# HT_Device.net
KiCad netlist of a schematic drawn in Altium Designer
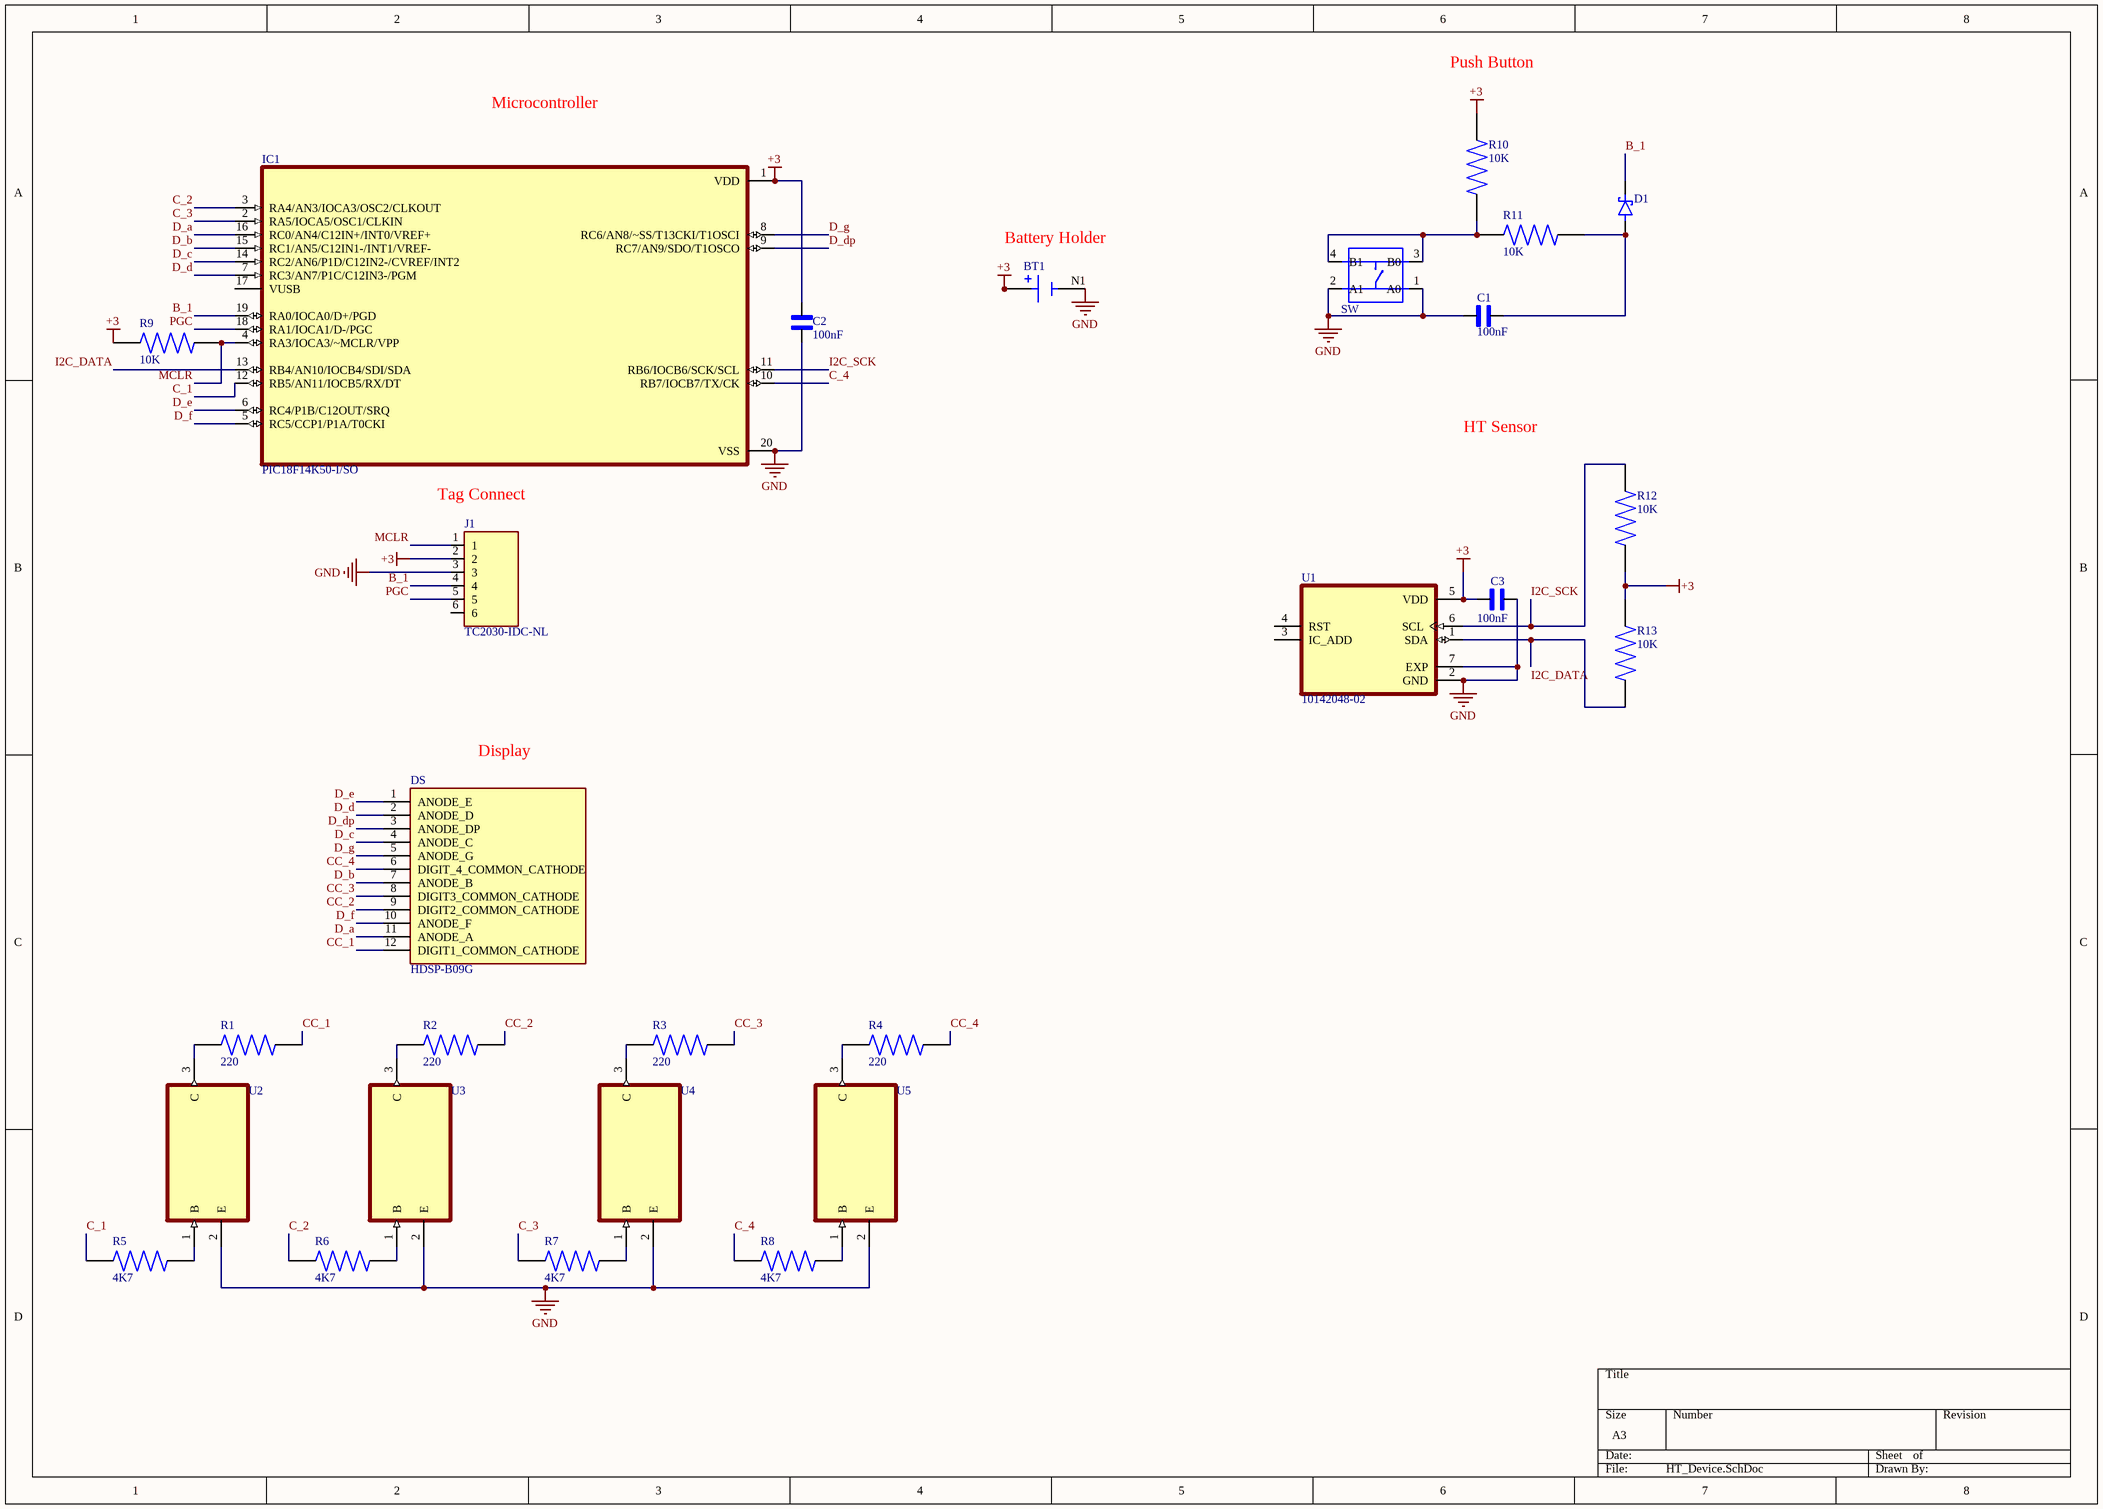
[diagram p0: HT_Device.SchDoc]

(export (version "E")
  (design (tool "Eeschema 10.0.6"))
  (components
    (comp (ref "BT1")
      (value "BAT-HLD-001")
      (footprint "BAT_BAT-HLD-001")
      (description "Battery Retainer Coin, 20.0mm 1 Cell SMD (SMT) Tab")
      (libsource (lib "BatteryHolder_CR2032") (part "BAT-HLD-001"))
    )
    (comp (ref "C1")
      (value "100nF")
      (footprint "WCAP-CSGP_885012207128")
      (fields (field (name "MP") "885012207128"))
      (libsource (lib "Capacitor_100nF_0805") (part "885012207128"))
    )
    (comp (ref "C2")
      (value "100nF")
      (footprint "WCAP-CSGP_885012207128")
      (fields (field (name "MP") "885012207128"))
      (libsource (lib "") (part "885012207128_1"))
    )
    (comp (ref "C3")
      (value "100nF")
      (footprint "WCAP-CSGP_885012207128")
      (fields (field (name "MP") "885012207128"))
      (libsource (lib "Capacitor_100nF_0805") (part "885012207128"))
    )
    (comp (ref "D1")
      (value "1N5817-T")
      (footprint "DIOAD1039W78L463D236")
      (description "Diode Schottky 20 V 1A Through Hole DO-41")
      (fields (field (name "MF") "Diodes Inc."))
      (libsource (lib "Diode_Rectifier_Schottky02") (part "1N5817-T"))
    )
    (comp (ref "DS")
      (value "HDSP-B09G")
      (footprint "AVAGO_HDSP-B09G")
      (fields (field (name "MF") "Broadcom Limited"))
      (libsource (lib "7Segment_4DigitalDisplay") (part "HDSP-B09G"))
    )
    (comp (ref "IC1")
      (value "PIC18F14K50-I/SO")
      (footprint "SOIC127P1032X265-20N")
      (description "PIC PICÂ® XLPâ„¢ 18K Microcontroller IC 8-Bit 48MHz 16KB _8K x 16_ FLASH 20-SOIC")
      (fields (field (name "MF") "Microchip"))
      (libsource (lib "SnapEDAsch") (part "PIC18F14K50-I/SO"))
    )
    (comp (ref "J1")
      (value "TC2030-IDC-NL")
      (footprint "TAG_TC2030-IDC-NL")
      (description "CABLE ADAPTER 6 POS")
      (libsource (lib "TagConnectPin_TC2030-IDC-NL") (part "TC2030-IDC-NL"))
    )
    (comp (ref "R1")
      (value "220")
      (footprint "RES_ERJP06J221V")
      (fields (field (name "MP") "ERJP06J221V"))
      (libsource (lib "Resistor_220_0805") (part "ERJP06J221V"))
    )
    (comp (ref "R2")
      (value "220")
      (footprint "RES_ERJP06J221V")
      (fields (field (name "MP") "ERJP06J221V"))
      (libsource (lib "Resistor_220_0805") (part "ERJP06J221V"))
    )
    (comp (ref "R3")
      (value "220")
      (footprint "RES_ERJP06J221V")
      (fields (field (name "MP") "ERJP06J221V"))
      (libsource (lib "Resistor_220_0805") (part "ERJP06J221V"))
    )
    (comp (ref "R4")
      (value "220")
      (footprint "RES_ERJP06J221V")
      (fields (field (name "MP") "ERJP06J221V"))
      (libsource (lib "Resistor_220_0805") (part "ERJP06J221V"))
    )
    (comp (ref "R5")
      (value "4K7")
      (footprint "RESC2012X55N")
      (fields (field (name "MP") "TNPW08054K70BXTA"))
      (libsource (lib "Resistor_4K7_0805") (part "TNPW08054K70BXTA"))
    )
    (comp (ref "R6")
      (value "4K7")
      (footprint "RESC2012X55N")
      (fields (field (name "MP") "TNPW08054K70BXTA"))
      (libsource (lib "Resistor_4K7_0805") (part "TNPW08054K70BXTA"))
    )
    (comp (ref "R7")
      (value "4K7")
      (footprint "RESC2012X55N")
      (fields (field (name "MP") "TNPW08054K70BXTA"))
      (libsource (lib "Resistor_4K7_0805") (part "TNPW08054K70BXTA"))
    )
    (comp (ref "R8")
      (value "4K7")
      (footprint "RESC2012X55N")
      (fields (field (name "MP") "TNPW08054K70BXTA"))
      (libsource (lib "Resistor_4K7_0805") (part "TNPW08054K70BXTA"))
    )
    (comp (ref "R9")
      (value "10K")
      (footprint "RESC2012X65N")
      (description "CRG0805 1% 10K")
      (fields (field (name "MF") "TE Connectivity") (field (name "TOLERANCE") "1%"))
      (libsource (lib "Resistor_10K_0805") (part "CRG0805F10K"))
    )
    (comp (ref "R10")
      (value "10K")
      (footprint "RESC2012X65N")
      (description "CRG0805 1% 10K")
      (fields (field (name "MF") "TE Connectivity") (field (name "TOLERANCE") "1%"))
      (libsource (lib "Resistor_10K_0805") (part "CRG0805F10K"))
    )
    (comp (ref "R11")
      (value "10K")
      (footprint "RESC2012X65N")
      (description "CRG0805 1% 10K")
      (fields (field (name "MF") "TE Connectivity") (field (name "TOLERANCE") "1%"))
      (libsource (lib "Resistor_10K_0805") (part "CRG0805F10K"))
    )
    (comp (ref "R12")
      (value "10K")
      (footprint "RESC2012X65N")
      (description "CRG0805 1% 10K")
      (fields (field (name "MF") "TE Connectivity") (field (name "TOLERANCE") "1%"))
      (libsource (lib "Resistor_10K_0805") (part "CRG0805F10K"))
    )
    (comp (ref "R13")
      (value "10K")
      (footprint "RESC2012X65N")
      (description "CRG0805 1% 10K")
      (fields (field (name "MF") "TE Connectivity") (field (name "TOLERANCE") "1%"))
      (libsource (lib "Resistor_10K_0805") (part "CRG0805F10K"))
    )
    (comp (ref "SW")
      (value "SMD-BUTTON(4P-5.2X5.2X1.5MM-SKQGADE010)")
      (footprint "SW4-SMD-5.2X5.2X1.5MM")
      (description "Switch Tactile N.O. SPST Round Button Gull Wing 0.05A 12VDC 2.55N SMD T/R")
      (fields (field (name "MF") "ALPS") (field (name "MP") "SKQGADE010"))
      (libsource (lib "PushButton04_4Pin") (part "SMD-BUTTON(4P-5.2X5.2X1.5MM-SKQGADE010)"))
    )
    (comp (ref "U1")
      (value "10142048-02")
      (footprint "SON80P250X250X100-7N_10142048-02")
      (description "Digital Relative Humidity sensor with Temperature output")
      (libsource (lib "10142048-02") (part "10142048-02"))
    )
    (comp (ref "U2")
      (value "MMBT2222A-7-F")
      (footprint "SOT103P240X110-3N")
      (description "Bipolar _BJT_ Transistor NPN 40V 600mA 300MHz 310mW Surface Mount SOT-23-3")
      (fields (field (name "MF") "Diodes Inc.") (field (name "DIGI-KEY_PART_NUMBER") "MMBT2222A-FDICT-ND"))
      (libsource (lib "BJT_NPN_600mA") (part "MMBT2222A-7-F"))
    )
    (comp (ref "U3")
      (value "MMBT2222A-7-F")
      (footprint "SOT103P240X110-3N")
      (description "Bipolar _BJT_ Transistor NPN 40V 600mA 300MHz 310mW Surface Mount SOT-23-3")
      (fields (field (name "MF") "Diodes Inc.") (field (name "DIGI-KEY_PART_NUMBER") "MMBT2222A-FDICT-ND"))
      (libsource (lib "BJT_NPN_600mA") (part "MMBT2222A-7-F"))
    )
    (comp (ref "U4")
      (value "MMBT2222A-7-F")
      (footprint "SOT103P240X110-3N")
      (description "Bipolar _BJT_ Transistor NPN 40V 600mA 300MHz 310mW Surface Mount SOT-23-3")
      (fields (field (name "MF") "Diodes Inc.") (field (name "DIGI-KEY_PART_NUMBER") "MMBT2222A-FDICT-ND"))
      (libsource (lib "BJT_NPN_600mA") (part "MMBT2222A-7-F"))
    )
    (comp (ref "U5")
      (value "MMBT2222A-7-F")
      (footprint "SOT103P240X110-3N")
      (description "Bipolar _BJT_ Transistor NPN 40V 600mA 300MHz 310mW Surface Mount SOT-23-3")
      (fields (field (name "MF") "Diodes Inc.") (field (name "DIGI-KEY_PART_NUMBER") "MMBT2222A-FDICT-ND"))
      (libsource (lib "BJT_NPN_600mA") (part "MMBT2222A-7-F"))
    )
  )
  (nets
    (net (code "1") (name "+3") (class "Default")
      (node (ref "BT1") (pin "P1") (pinfunction "POS_P1") (pintype "passive"))
      (node (ref "BT1") (pin "P2") (pinfunction "POS_P2") (pintype "passive"))
      (node (ref "C2") (pin "2") (pinfunction "2_2") (pintype "passive"))
      (node (ref "C3") (pin "2") (pinfunction "2_2") (pintype "passive"))
      (node (ref "IC1") (pin "1") (pinfunction "VDD_1") (pintype "power_in"))
      (node (ref "J1") (pin "2") (pinfunction "2_2") (pintype "passive"))
      (node (ref "R10") (pin "2") (pinfunction "2_2") (pintype "passive"))
      (node (ref "R12") (pin "1") (pinfunction "1_1") (pintype "passive"))
      (node (ref "R13") (pin "2") (pinfunction "2_2") (pintype "passive"))
      (node (ref "R9") (pin "1") (pinfunction "1_1") (pintype "passive"))
      (node (ref "U1") (pin "5") (pinfunction "VDD_5") (pintype "power_in"))
    )
    (net (code "2") (name "/B_1") (class "Default")
      (node (ref "D1") (pin "1") (pinfunction "K_1") (pintype "passive"))
      (node (ref "IC1") (pin "19") (pinfunction "RA0/IOCA0/D+/PGD_19") (pintype "bidirectional"))
      (node (ref "J1") (pin "4") (pinfunction "4_4") (pintype "passive"))
    )
    (net (code "3") (name "/CC_1") (class "Default")
      (node (ref "DS") (pin "12") (pinfunction "DIGIT1_COMMON_CATHODE_12") (pintype "passive"))
      (node (ref "R1") (pin "2") (pinfunction "2_2") (pintype "passive"))
    )
    (net (code "4") (name "/CC_2") (class "Default")
      (node (ref "DS") (pin "9") (pinfunction "DIGIT2_COMMON_CATHODE_9") (pintype "passive"))
      (node (ref "R2") (pin "2") (pinfunction "2_2") (pintype "passive"))
    )
    (net (code "5") (name "/CC_3") (class "Default")
      (node (ref "DS") (pin "8") (pinfunction "DIGIT3_COMMON_CATHODE_8") (pintype "passive"))
      (node (ref "R3") (pin "2") (pinfunction "2_2") (pintype "passive"))
    )
    (net (code "6") (name "/CC_4") (class "Default")
      (node (ref "DS") (pin "6") (pinfunction "DIGIT_4_COMMON_CATHODE_6") (pintype "passive"))
      (node (ref "R4") (pin "2") (pinfunction "2_2") (pintype "passive"))
    )
    (net (code "7") (name "/C_1") (class "Default")
      (node (ref "IC1") (pin "12") (pinfunction "RB5/AN11/IOCB5/RX/DT_12") (pintype "bidirectional"))
      (node (ref "R5") (pin "1") (pinfunction "1_1") (pintype "passive"))
    )
    (net (code "8") (name "/C_2") (class "Default")
      (node (ref "IC1") (pin "3") (pinfunction "RA4/AN3/IOCA3/OSC2/CLKOUT_3") (pintype "input"))
      (node (ref "R6") (pin "1") (pinfunction "1_1") (pintype "passive"))
    )
    (net (code "9") (name "/C_3") (class "Default")
      (node (ref "IC1") (pin "2") (pinfunction "RA5/IOCA5/OSC1/CLKIN_2") (pintype "input"))
      (node (ref "R7") (pin "1") (pinfunction "1_1") (pintype "passive"))
    )
    (net (code "10") (name "/C_4") (class "Default")
      (node (ref "IC1") (pin "10") (pinfunction "RB7/IOCB7/TX/CK_10") (pintype "bidirectional"))
      (node (ref "R8") (pin "1") (pinfunction "1_1") (pintype "passive"))
    )
    (net (code "11") (name "/D_a") (class "Default")
      (node (ref "DS") (pin "11") (pinfunction "ANODE_A_11") (pintype "passive"))
      (node (ref "IC1") (pin "16") (pinfunction "RC0/AN4/C12IN+/INT0/VREF+_16") (pintype "input"))
    )
    (net (code "12") (name "/D_b") (class "Default")
      (node (ref "DS") (pin "7") (pinfunction "ANODE_B_7") (pintype "passive"))
      (node (ref "IC1") (pin "15") (pinfunction "RC1/AN5/C12IN1-/INT1/VREF-_15") (pintype "input"))
    )
    (net (code "13") (name "/D_c") (class "Default")
      (node (ref "DS") (pin "4") (pinfunction "ANODE_C_4") (pintype "passive"))
      (node (ref "IC1") (pin "14") (pinfunction "RC2/AN6/P1D/C12IN2-/CVREF/INT2_14") (pintype "input"))
    )
    (net (code "14") (name "/D_d") (class "Default")
      (node (ref "DS") (pin "2") (pinfunction "ANODE_D_2") (pintype "passive"))
      (node (ref "IC1") (pin "7") (pinfunction "RC3/AN7/P1C/C12IN3-/PGM_7") (pintype "input"))
    )
    (net (code "15") (name "/D_dp") (class "Default")
      (node (ref "DS") (pin "3") (pinfunction "ANODE_DP_3") (pintype "passive"))
      (node (ref "IC1") (pin "9") (pinfunction "RC7/AN9/SDO/T1OSCO_9") (pintype "bidirectional"))
    )
    (net (code "16") (name "/D_e") (class "Default")
      (node (ref "DS") (pin "1") (pinfunction "ANODE_E_1") (pintype "passive"))
      (node (ref "IC1") (pin "6") (pinfunction "RC4/P1B/C12OUT/SRQ_6") (pintype "bidirectional"))
    )
    (net (code "17") (name "/D_f") (class "Default")
      (node (ref "DS") (pin "10") (pinfunction "ANODE_F_10") (pintype "passive"))
      (node (ref "IC1") (pin "5") (pinfunction "RC5/CCP1/P1A/T0CKI_5") (pintype "bidirectional"))
    )
    (net (code "18") (name "/D_g") (class "Default")
      (node (ref "DS") (pin "5") (pinfunction "ANODE_G_5") (pintype "passive"))
      (node (ref "IC1") (pin "8") (pinfunction "RC6/AN8/~SS/T13CKI/T1OSCI_8") (pintype "bidirectional"))
    )
    (net (code "19") (name "/I2C_DATA") (class "Default")
      (node (ref "IC1") (pin "13") (pinfunction "RB4/AN10/IOCB4/SDI/SDA_13") (pintype "bidirectional"))
      (node (ref "R13") (pin "1") (pinfunction "1_1") (pintype "passive"))
      (node (ref "U1") (pin "1") (pinfunction "SDA_1") (pintype "bidirectional"))
    )
    (net (code "20") (name "/I2C_SCK") (class "Default")
      (node (ref "IC1") (pin "11") (pinfunction "RB6/IOCB6/SCK/SCL_11") (pintype "bidirectional"))
      (node (ref "R12") (pin "2") (pinfunction "2_2") (pintype "passive"))
      (node (ref "U1") (pin "6") (pinfunction "SCL_6") (pintype "input"))
    )
    (net (code "21") (name "/MCLR") (class "Default")
      (node (ref "IC1") (pin "4") (pinfunction "RA3/IOCA3/~MCLR/VPP_4") (pintype "bidirectional"))
      (node (ref "J1") (pin "1") (pinfunction "1_1") (pintype "passive"))
      (node (ref "R9") (pin "2") (pinfunction "2_2") (pintype "passive"))
    )
    (net (code "22") (name "/PGC") (class "Default")
      (node (ref "IC1") (pin "18") (pinfunction "RA1/IOCA1/D-/PGC_18") (pintype "bidirectional"))
      (node (ref "J1") (pin "5") (pinfunction "5_5") (pintype "passive"))
    )
    (net (code "23") (name "GND") (class "Default")
      (node (ref "BT1") (pin "N1") (pinfunction "NEG_N1") (pintype "passive"))
      (node (ref "C1") (pin "2") (pinfunction "2_2") (pintype "passive"))
      (node (ref "C2") (pin "1") (pinfunction "1_1") (pintype "passive"))
      (node (ref "C3") (pin "1") (pinfunction "1_1") (pintype "passive"))
      (node (ref "IC1") (pin "20") (pinfunction "VSS_20") (pintype "power_in"))
      (node (ref "J1") (pin "3") (pinfunction "3_3") (pintype "passive"))
      (node (ref "SW") (pin "1") (pinfunction "A0_1") (pintype "bidirectional"))
      (node (ref "SW") (pin "2") (pinfunction "A1_2") (pintype "bidirectional"))
      (node (ref "U1") (pin "2") (pinfunction "GND_2") (pintype "power_in"))
      (node (ref "U1") (pin "7") (pinfunction "EXP_7") (pintype "passive"))
      (node (ref "U2") (pin "2") (pinfunction "E_2") (pintype "passive"))
      (node (ref "U3") (pin "2") (pinfunction "E_2") (pintype "passive"))
      (node (ref "U4") (pin "2") (pinfunction "E_2") (pintype "passive"))
      (node (ref "U5") (pin "2") (pinfunction "E_2") (pintype "passive"))
    )
    (net (code "24") (name "Net-(D1-A)") (class "Default")
      (node (ref "C1") (pin "1") (pinfunction "1_1") (pintype "passive"))
      (node (ref "D1") (pin "2") (pinfunction "A_2") (pintype "passive"))
      (node (ref "R11") (pin "2") (pinfunction "2_2") (pintype "passive"))
    )
    (net (code "25") (name "Net-(SW-B0)") (class "Default")
      (node (ref "R10") (pin "1") (pinfunction "1_1") (pintype "passive"))
      (node (ref "R11") (pin "1") (pinfunction "1_1") (pintype "passive"))
      (node (ref "SW") (pin "3") (pinfunction "B0_3") (pintype "bidirectional"))
      (node (ref "SW") (pin "4") (pinfunction "B1_4") (pintype "bidirectional"))
    )
    (net (code "26") (name "Net-(U2-B)") (class "Default")
      (node (ref "R5") (pin "2") (pinfunction "2_2") (pintype "passive"))
      (node (ref "U2") (pin "1") (pinfunction "B_1") (pintype "input"))
    )
    (net (code "27") (name "Net-(U2-C)") (class "Default")
      (node (ref "R1") (pin "1") (pinfunction "1_1") (pintype "passive"))
      (node (ref "U2") (pin "3") (pinfunction "C_3") (pintype "output"))
    )
    (net (code "28") (name "Net-(U3-B)") (class "Default")
      (node (ref "R6") (pin "2") (pinfunction "2_2") (pintype "passive"))
      (node (ref "U3") (pin "1") (pinfunction "B_1") (pintype "input"))
    )
    (net (code "29") (name "Net-(U3-C)") (class "Default")
      (node (ref "R2") (pin "1") (pinfunction "1_1") (pintype "passive"))
      (node (ref "U3") (pin "3") (pinfunction "C_3") (pintype "output"))
    )
    (net (code "30") (name "Net-(U4-B)") (class "Default")
      (node (ref "R7") (pin "2") (pinfunction "2_2") (pintype "passive"))
      (node (ref "U4") (pin "1") (pinfunction "B_1") (pintype "input"))
    )
    (net (code "31") (name "Net-(U4-C)") (class "Default")
      (node (ref "R3") (pin "1") (pinfunction "1_1") (pintype "passive"))
      (node (ref "U4") (pin "3") (pinfunction "C_3") (pintype "output"))
    )
    (net (code "32") (name "Net-(U5-B)") (class "Default")
      (node (ref "R8") (pin "2") (pinfunction "2_2") (pintype "passive"))
      (node (ref "U5") (pin "1") (pinfunction "B_1") (pintype "input"))
    )
    (net (code "33") (name "Net-(U5-C)") (class "Default")
      (node (ref "R4") (pin "1") (pinfunction "1_1") (pintype "passive"))
      (node (ref "U5") (pin "3") (pinfunction "C_3") (pintype "output"))
    )
    (net (code "34") (name "unconnected-(IC1-VUSB-Pad17)") (class "Default")
      (node (ref "IC1") (pin "17") (pinfunction "VUSB_17") (pintype "passive"))
    )
    (net (code "35") (name "unconnected-(J1-Pad6)") (class "Default")
      (node (ref "J1") (pin "6") (pinfunction "6_6") (pintype "passive"))
    )
    (net (code "36") (name "unconnected-(U1-IC_ADD-Pad3)") (class "Default")
      (node (ref "U1") (pin "3") (pinfunction "IC_ADD_3") (pintype "passive"))
    )
    (net (code "37") (name "unconnected-(U1-RST-Pad4)") (class "Default")
      (node (ref "U1") (pin "4") (pinfunction "RST_4") (pintype "passive"))
    )
  )
)
